# design.net
KiCad netlist of a schematic drawn in Altium Designer
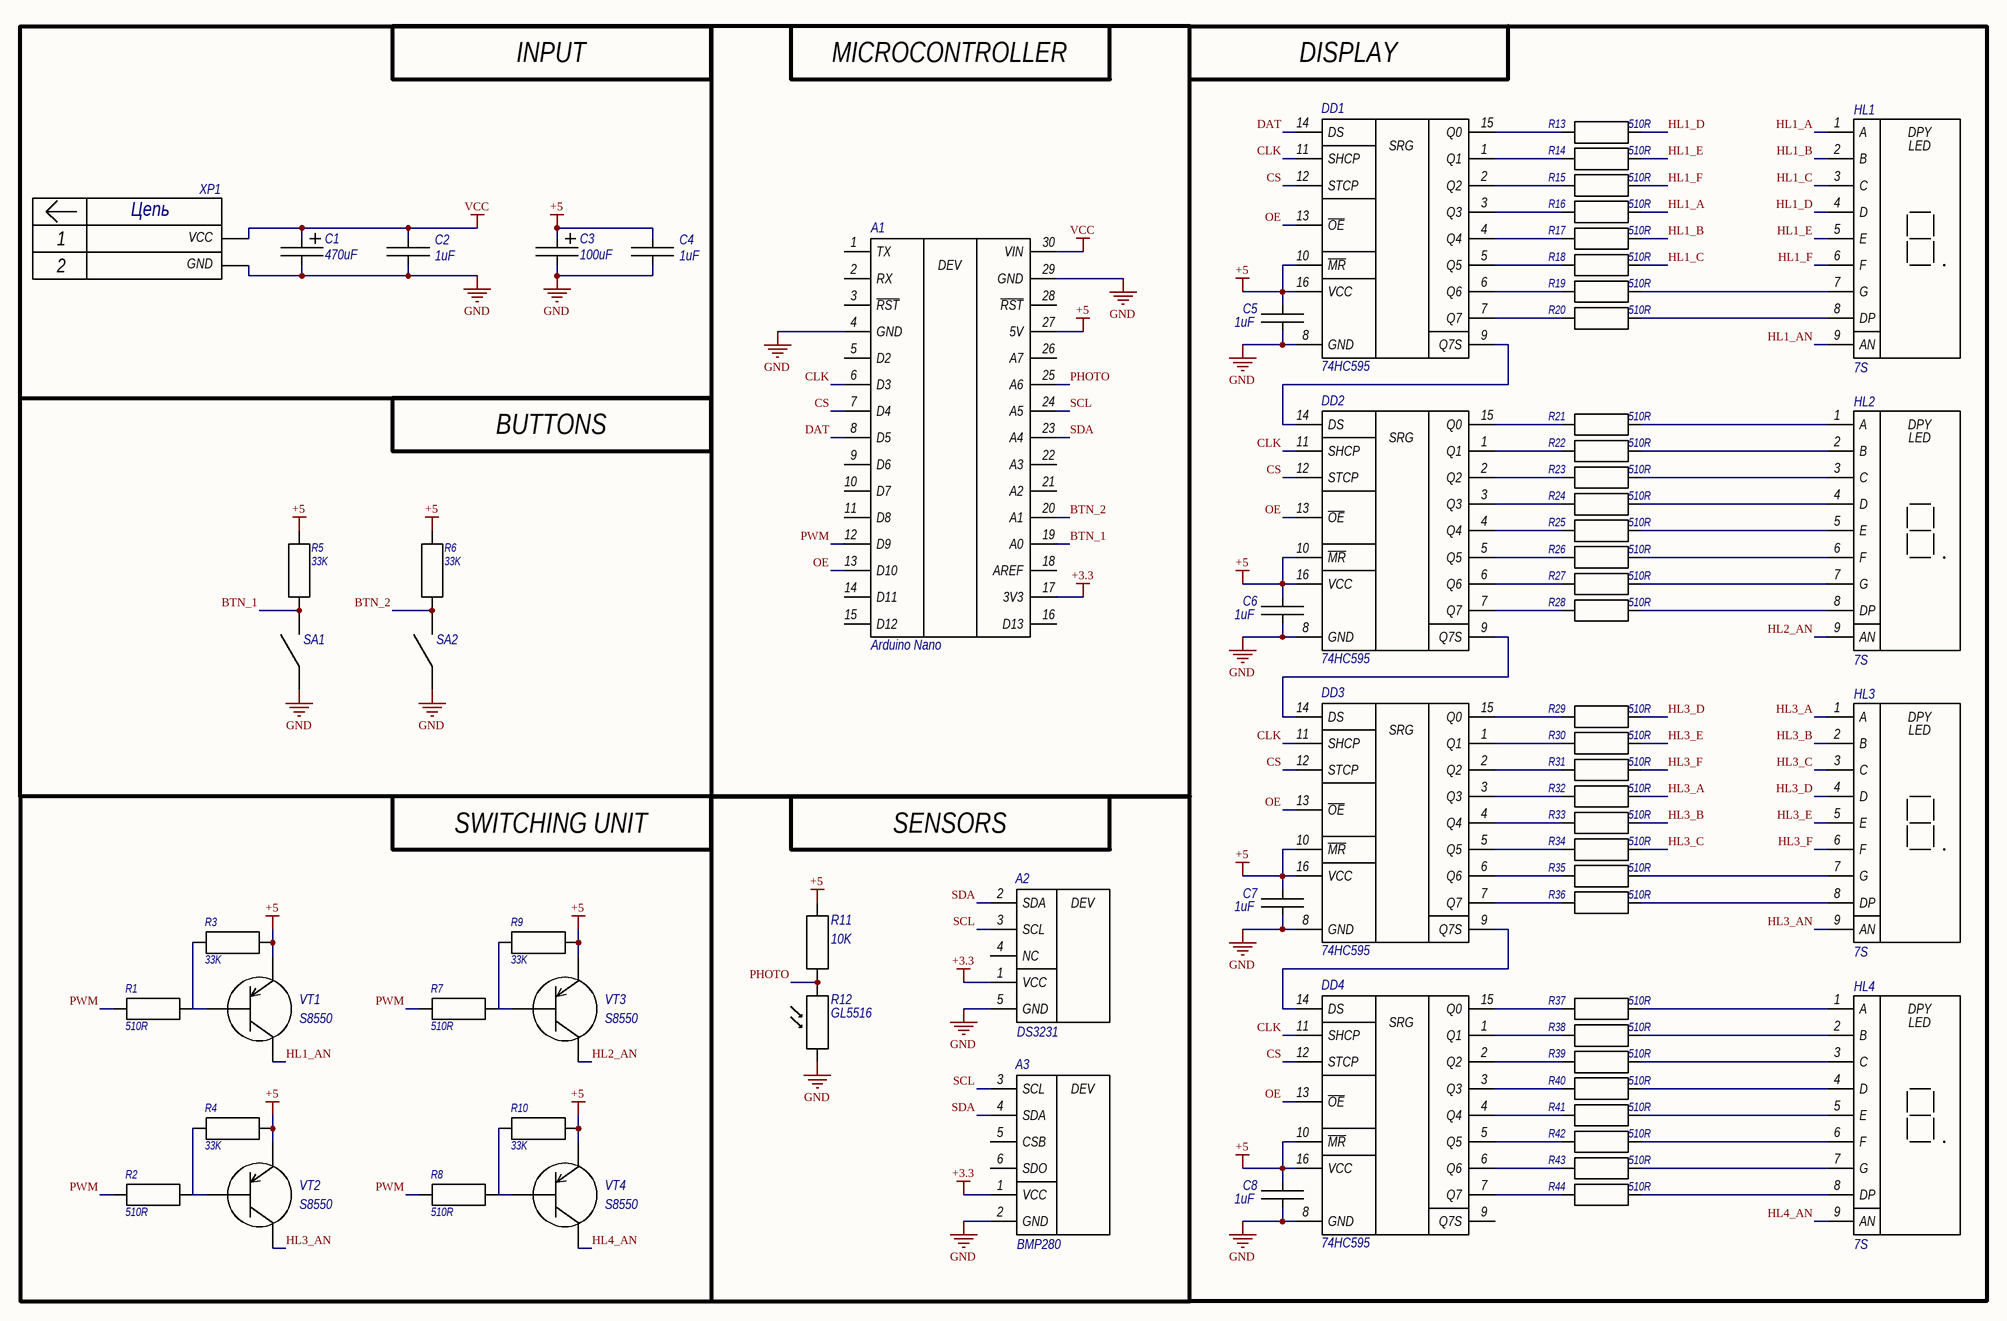
[diagram p0: Схема_часов.SchDoc]

(export (version "E")
  (design (tool "Eeschema 10.0.6"))
  (components
    (comp (ref "A1")
      (value "Arduino Nano")
      (footprint "ArduinoNano")
      (libsource (lib "Schlib1") (part "ArduinoNano"))
    )
    (comp (ref "A2")
      (value "DS3231")
      (footprint "DS3231micro")
      (libsource (lib "Schlib1") (part "DS3231micro"))
    )
    (comp (ref "A3")
      (value "BMP280")
      (footprint "BMP280_Module")
      (libsource (lib "Schlib1") (part "BMP280_Module"))
    )
    (comp (ref "C1")
      (value "470uF")
      (footprint "CAPAER_D0650_L1150_P0250_W50X300")
      (libsource (lib "Schlib1") (part "CPol"))
    )
    (comp (ref "C2")
      (value "1uF")
      (footprint "C0603")
      (description "Ceramic SMT, L*W 1.6x0.8mm, H=(0.8, 0.6)mm")
      (libsource (lib "Schlib1") (part "C0603"))
    )
    (comp (ref "C3")
      (value "100uF")
      (footprint "CAPAE_R0500_X0540(Nich_Case-C5)")
      (libsource (lib "Schlib1") (part "CPol"))
    )
    (comp (ref "C4")
      (value "1uF")
      (footprint "C0603")
      (description "Ceramic SMT, L*W 1.6x0.8mm, H=(0.8, 0.6)mm")
      (libsource (lib "Schlib1") (part "C0603"))
    )
    (comp (ref "C5")
      (value "1uF")
      (footprint "C0603")
      (description "Ceramic SMT, L*W 1.6x0.8mm, H=(0.8, 0.6)mm")
      (libsource (lib "Schlib1") (part "C0603"))
    )
    (comp (ref "C6")
      (value "1uF")
      (footprint "C0603")
      (description "Ceramic SMT, L*W 1.6x0.8mm, H=(0.8, 0.6)mm")
      (libsource (lib "Schlib1") (part "C0603"))
    )
    (comp (ref "C7")
      (value "1uF")
      (footprint "C0603")
      (description "Ceramic SMT, L*W 1.6x0.8mm, H=(0.8, 0.6)mm")
      (libsource (lib "Schlib1") (part "C0603"))
    )
    (comp (ref "C8")
      (value "1uF")
      (footprint "C0603")
      (description "Ceramic SMT, L*W 1.6x0.8mm, H=(0.8, 0.6)mm")
      (libsource (lib "Schlib1") (part "C0603"))
    )
    (comp (ref "DD1") (value "74HC595") (footprint "SO-16") (libsource (lib "Schlib1") (part "74HC595")))
    (comp (ref "DD2") (value "74HC595") (footprint "SO-16") (libsource (lib "Schlib1") (part "74HC595")))
    (comp (ref "DD3") (value "74HC595") (footprint "SO-16") (libsource (lib "Schlib1") (part "74HC595")))
    (comp (ref "DD4") (value "74HC595") (footprint "SO-16") (libsource (lib "Schlib1") (part "74HC595")))
    (comp (ref "HL1") (value "7S") (footprint "7SEG_SA10_21") (libsource (lib "Schlib1") (part "7SEG_AN")))
    (comp (ref "HL2") (value "7S") (footprint "7SEG_SA10_21") (libsource (lib "Schlib1") (part "7SEG_AN")))
    (comp (ref "HL3") (value "7S") (footprint "7SEG_SA10_21") (libsource (lib "Schlib1") (part "7SEG_AN")))
    (comp (ref "HL4") (value "7S") (footprint "7SEG_SA10_21") (libsource (lib "Schlib1") (part "7SEG_AN")))
    (comp (ref "R1")
      (value "510R")
      (footprint "R0805")
      (description "SMT, L*W 2.0x1.25mm, H=0.5mm")
      (libsource (lib "Schlib1") (part "R0805"))
    )
    (comp (ref "R2")
      (value "510R")
      (footprint "R0805")
      (description "SMT, L*W 2.0x1.25mm, H=0.5mm")
      (libsource (lib "Schlib1") (part "R0805"))
    )
    (comp (ref "R3")
      (value "33K")
      (footprint "R0805")
      (description "SMT, L*W 2.0x1.25mm, H=0.5mm")
      (libsource (lib "Schlib1") (part "R0805"))
    )
    (comp (ref "R4")
      (value "33K")
      (footprint "R0805")
      (description "SMT, L*W 2.0x1.25mm, H=0.5mm")
      (libsource (lib "Schlib1") (part "R0805"))
    )
    (comp (ref "R5")
      (value "33K")
      (footprint "R0805")
      (description "SMT, L*W 2.0x1.25mm, H=0.5mm")
      (libsource (lib "Schlib1") (part "R0805"))
    )
    (comp (ref "R6")
      (value "33K")
      (footprint "R0805")
      (description "SMT, L*W 2.0x1.25mm, H=0.5mm")
      (libsource (lib "Schlib1") (part "R0805"))
    )
    (comp (ref "R7")
      (value "510R")
      (footprint "R0805")
      (description "SMT, L*W 2.0x1.25mm, H=0.5mm")
      (libsource (lib "Schlib1") (part "R0805"))
    )
    (comp (ref "R8")
      (value "510R")
      (footprint "R0805")
      (description "SMT, L*W 2.0x1.25mm, H=0.5mm")
      (libsource (lib "Schlib1") (part "R0805"))
    )
    (comp (ref "R9")
      (value "33K")
      (footprint "R0805")
      (description "SMT, L*W 2.0x1.25mm, H=0.5mm")
      (libsource (lib "Schlib1") (part "R0805"))
    )
    (comp (ref "R10")
      (value "33K")
      (footprint "R0805")
      (description "SMT, L*W 2.0x1.25mm, H=0.5mm")
      (libsource (lib "Schlib1") (part "R0805"))
    )
    (comp (ref "R11")
      (value "10K")
      (footprint "R0805")
      (description "SMT, L*W 2.0x1.25mm, H=0.5mm")
      (libsource (lib "Schlib1") (part "R0805"))
    )
    (comp (ref "R12") (value "GL5516") (footprint "GL55") (libsource (lib "Schlib1") (part "Photores")))
    (comp (ref "R13")
      (value "510R")
      (footprint "R0805")
      (description "SMT, L*W 2.0x1.25mm, H=0.5mm")
      (libsource (lib "Schlib1") (part "R0805"))
    )
    (comp (ref "R14")
      (value "510R")
      (footprint "R0805")
      (description "SMT, L*W 2.0x1.25mm, H=0.5mm")
      (libsource (lib "Schlib1") (part "R0805"))
    )
    (comp (ref "R15")
      (value "510R")
      (footprint "R0805")
      (description "SMT, L*W 2.0x1.25mm, H=0.5mm")
      (libsource (lib "Schlib1") (part "R0805"))
    )
    (comp (ref "R16")
      (value "510R")
      (footprint "R0805")
      (description "SMT, L*W 2.0x1.25mm, H=0.5mm")
      (libsource (lib "Schlib1") (part "R0805"))
    )
    (comp (ref "R17")
      (value "510R")
      (footprint "R0805")
      (description "SMT, L*W 2.0x1.25mm, H=0.5mm")
      (libsource (lib "Schlib1") (part "R0805"))
    )
    (comp (ref "R18")
      (value "510R")
      (footprint "R0805")
      (description "SMT, L*W 2.0x1.25mm, H=0.5mm")
      (libsource (lib "Schlib1") (part "R0805"))
    )
    (comp (ref "R19")
      (value "510R")
      (footprint "R0805")
      (description "SMT, L*W 2.0x1.25mm, H=0.5mm")
      (libsource (lib "Schlib1") (part "R0805"))
    )
    (comp (ref "R20")
      (value "510R")
      (footprint "R0805")
      (description "SMT, L*W 2.0x1.25mm, H=0.5mm")
      (libsource (lib "Schlib1") (part "R0805"))
    )
    (comp (ref "R21")
      (value "510R")
      (footprint "R0805")
      (description "SMT, L*W 2.0x1.25mm, H=0.5mm")
      (libsource (lib "Schlib1") (part "R0805"))
    )
    (comp (ref "R22")
      (value "510R")
      (footprint "R0805")
      (description "SMT, L*W 2.0x1.25mm, H=0.5mm")
      (libsource (lib "Schlib1") (part "R0805"))
    )
    (comp (ref "R23")
      (value "510R")
      (footprint "R0805")
      (description "SMT, L*W 2.0x1.25mm, H=0.5mm")
      (libsource (lib "Schlib1") (part "R0805"))
    )
    (comp (ref "R24")
      (value "510R")
      (footprint "R0805")
      (description "SMT, L*W 2.0x1.25mm, H=0.5mm")
      (libsource (lib "Schlib1") (part "R0805"))
    )
    (comp (ref "R25")
      (value "510R")
      (footprint "R0805")
      (description "SMT, L*W 2.0x1.25mm, H=0.5mm")
      (libsource (lib "Schlib1") (part "R0805"))
    )
    (comp (ref "R26")
      (value "510R")
      (footprint "R0805")
      (description "SMT, L*W 2.0x1.25mm, H=0.5mm")
      (libsource (lib "Schlib1") (part "R0805"))
    )
    (comp (ref "R27")
      (value "510R")
      (footprint "R0805")
      (description "SMT, L*W 2.0x1.25mm, H=0.5mm")
      (libsource (lib "Schlib1") (part "R0805"))
    )
    (comp (ref "R28")
      (value "510R")
      (footprint "R0805")
      (description "SMT, L*W 2.0x1.25mm, H=0.5mm")
      (libsource (lib "Schlib1") (part "R0805"))
    )
    (comp (ref "R29")
      (value "510R")
      (footprint "R0805")
      (description "SMT, L*W 2.0x1.25mm, H=0.5mm")
      (libsource (lib "Schlib1") (part "R0805"))
    )
    (comp (ref "R30")
      (value "510R")
      (footprint "R0805")
      (description "SMT, L*W 2.0x1.25mm, H=0.5mm")
      (libsource (lib "Schlib1") (part "R0805"))
    )
    (comp (ref "R31")
      (value "510R")
      (footprint "R0805")
      (description "SMT, L*W 2.0x1.25mm, H=0.5mm")
      (libsource (lib "Schlib1") (part "R0805"))
    )
    (comp (ref "R32")
      (value "510R")
      (footprint "R0805")
      (description "SMT, L*W 2.0x1.25mm, H=0.5mm")
      (libsource (lib "Schlib1") (part "R0805"))
    )
    (comp (ref "R33")
      (value "510R")
      (footprint "R0805")
      (description "SMT, L*W 2.0x1.25mm, H=0.5mm")
      (libsource (lib "Schlib1") (part "R0805"))
    )
    (comp (ref "R34")
      (value "510R")
      (footprint "R0805")
      (description "SMT, L*W 2.0x1.25mm, H=0.5mm")
      (libsource (lib "Schlib1") (part "R0805"))
    )
    (comp (ref "R35")
      (value "510R")
      (footprint "R0805")
      (description "SMT, L*W 2.0x1.25mm, H=0.5mm")
      (libsource (lib "Schlib1") (part "R0805"))
    )
    (comp (ref "R36")
      (value "510R")
      (footprint "R0805")
      (description "SMT, L*W 2.0x1.25mm, H=0.5mm")
      (libsource (lib "Schlib1") (part "R0805"))
    )
    (comp (ref "R37")
      (value "510R")
      (footprint "R0805")
      (description "SMT, L*W 2.0x1.25mm, H=0.5mm")
      (libsource (lib "Schlib1") (part "R0805"))
    )
    (comp (ref "R38")
      (value "510R")
      (footprint "R0805")
      (description "SMT, L*W 2.0x1.25mm, H=0.5mm")
      (libsource (lib "Schlib1") (part "R0805"))
    )
    (comp (ref "R39")
      (value "510R")
      (footprint "R0805")
      (description "SMT, L*W 2.0x1.25mm, H=0.5mm")
      (libsource (lib "Schlib1") (part "R0805"))
    )
    (comp (ref "R40")
      (value "510R")
      (footprint "R0805")
      (description "SMT, L*W 2.0x1.25mm, H=0.5mm")
      (libsource (lib "Schlib1") (part "R0805"))
    )
    (comp (ref "R41")
      (value "510R")
      (footprint "R0805")
      (description "SMT, L*W 2.0x1.25mm, H=0.5mm")
      (libsource (lib "Schlib1") (part "R0805"))
    )
    (comp (ref "R42")
      (value "510R")
      (footprint "R0805")
      (description "SMT, L*W 2.0x1.25mm, H=0.5mm")
      (libsource (lib "Schlib1") (part "R0805"))
    )
    (comp (ref "R43")
      (value "510R")
      (footprint "R0805")
      (description "SMT, L*W 2.0x1.25mm, H=0.5mm")
      (libsource (lib "Schlib1") (part "R0805"))
    )
    (comp (ref "R44")
      (value "510R")
      (footprint "R0805")
      (description "SMT, L*W 2.0x1.25mm, H=0.5mm")
      (libsource (lib "Schlib1") (part "R0805"))
    )
    (comp (ref "SA1") (value "~") (footprint "TS6606-9.0") (libsource (lib "Schlib1") (part "SW")))
    (comp (ref "SA2") (value "~") (footprint "TS6606-9.0") (libsource (lib "Schlib1") (part "SW")))
    (comp (ref "VT1")
      (value "~")
      (footprint "S8550")
      (fields (field (name "MODEL") "S8550"))
      (libsource (lib "Schlib1") (part "TRANS-PNP"))
    )
    (comp (ref "VT2")
      (value "~")
      (footprint "S8550")
      (fields (field (name "MODEL") "S8550"))
      (libsource (lib "Schlib1") (part "TRANS-PNP"))
    )
    (comp (ref "VT3")
      (value "~")
      (footprint "S8550")
      (fields (field (name "MODEL") "S8550"))
      (libsource (lib "Schlib1") (part "TRANS-PNP"))
    )
    (comp (ref "VT4")
      (value "~")
      (footprint "S8550")
      (fields (field (name "MODEL") "S8550"))
      (libsource (lib "Schlib1") (part "TRANS-PNP"))
    )
    (comp (ref "XP1")
      (value "DS1072-2MVT6")
      (footprint "PLS2-2")
      (description "2-pin Straight connector PWL-2")
      (fields
        (field (name "MANUFACTURER") "Connfly")
        (field (name "VOLTAGE") "250Vac")
        (field (name "NET 2") "GND")
        (field (name "NET 1") "VCC")
      )
      (libsource (lib "Schlib1") (part "DS1072-2MVT6"))
    )
  )
  (nets
    (net (code "1") (name "+3.3") (class "Default")
      (node (ref "A1") (pin "17") (pinfunction "3V3_17") (pintype "passive"))
      (node (ref "A2") (pin "1") (pinfunction "VCC_1") (pintype "passive"))
      (node (ref "A3") (pin "1") (pinfunction "VCC_1") (pintype "passive"))
    )
    (net (code "2") (name "+5") (class "Default")
      (node (ref "A1") (pin "27") (pinfunction "5V_27") (pintype "passive"))
      (node (ref "C3") (pin "1") (pinfunction "1_1") (pintype "passive"))
      (node (ref "C4") (pin "2") (pinfunction "2_2") (pintype "passive"))
      (node (ref "C5") (pin "1") (pinfunction "1_1") (pintype "passive"))
      (node (ref "C6") (pin "1") (pinfunction "1_1") (pintype "passive"))
      (node (ref "C7") (pin "1") (pinfunction "1_1") (pintype "passive"))
      (node (ref "C8") (pin "1") (pinfunction "1_1") (pintype "passive"))
      (node (ref "DD1") (pin "10") (pinfunction "~{MR}_10") (pintype "passive"))
      (node (ref "DD1") (pin "16") (pinfunction "VCC_16") (pintype "passive"))
      (node (ref "DD2") (pin "10") (pinfunction "~{MR}_10") (pintype "passive"))
      (node (ref "DD2") (pin "16") (pinfunction "VCC_16") (pintype "passive"))
      (node (ref "DD3") (pin "10") (pinfunction "~{MR}_10") (pintype "passive"))
      (node (ref "DD3") (pin "16") (pinfunction "VCC_16") (pintype "passive"))
      (node (ref "DD4") (pin "10") (pinfunction "~{MR}_10") (pintype "passive"))
      (node (ref "DD4") (pin "16") (pinfunction "VCC_16") (pintype "passive"))
      (node (ref "R10") (pin "1") (pinfunction "1_1") (pintype "passive"))
      (node (ref "R11") (pin "1") (pinfunction "1_1") (pintype "passive"))
      (node (ref "R3") (pin "1") (pinfunction "1_1") (pintype "passive"))
      (node (ref "R4") (pin "1") (pinfunction "1_1") (pintype "passive"))
      (node (ref "R5") (pin "1") (pinfunction "1_1") (pintype "passive"))
      (node (ref "R6") (pin "1") (pinfunction "1_1") (pintype "passive"))
      (node (ref "R9") (pin "1") (pinfunction "1_1") (pintype "passive"))
      (node (ref "VT1") (pin "E") (pinfunction "E_E") (pintype "passive"))
      (node (ref "VT2") (pin "E") (pinfunction "E_E") (pintype "passive"))
      (node (ref "VT3") (pin "E") (pinfunction "E_E") (pintype "passive"))
      (node (ref "VT4") (pin "E") (pinfunction "E_E") (pintype "passive"))
    )
    (net (code "3") (name "/BTN_1") (class "Default")
      (node (ref "A1") (pin "19") (pinfunction "A0_19") (pintype "passive"))
      (node (ref "R5") (pin "2") (pinfunction "2_2") (pintype "passive"))
      (node (ref "SA1") (pin "1") (pinfunction "1_1") (pintype "passive"))
    )
    (net (code "4") (name "/BTN_2") (class "Default")
      (node (ref "A1") (pin "20") (pinfunction "A1_20") (pintype "passive"))
      (node (ref "R6") (pin "2") (pinfunction "2_2") (pintype "passive"))
      (node (ref "SA2") (pin "1") (pinfunction "1_1") (pintype "passive"))
    )
    (net (code "5") (name "/CLK") (class "Default")
      (node (ref "A1") (pin "6") (pinfunction "D3_6") (pintype "passive"))
      (node (ref "DD1") (pin "11") (pinfunction "SHCP_11") (pintype "passive"))
      (node (ref "DD2") (pin "11") (pinfunction "SHCP_11") (pintype "passive"))
      (node (ref "DD3") (pin "11") (pinfunction "SHCP_11") (pintype "passive"))
      (node (ref "DD4") (pin "11") (pinfunction "SHCP_11") (pintype "passive"))
    )
    (net (code "6") (name "/CS") (class "Default")
      (node (ref "A1") (pin "7") (pinfunction "D4_7") (pintype "passive"))
      (node (ref "DD1") (pin "12") (pinfunction "STCP_12") (pintype "passive"))
      (node (ref "DD2") (pin "12") (pinfunction "STCP_12") (pintype "passive"))
      (node (ref "DD3") (pin "12") (pinfunction "STCP_12") (pintype "passive"))
      (node (ref "DD4") (pin "12") (pinfunction "STCP_12") (pintype "passive"))
    )
    (net (code "7") (name "/DAT") (class "Default")
      (node (ref "A1") (pin "8") (pinfunction "D5_8") (pintype "passive"))
      (node (ref "DD1") (pin "14") (pinfunction "DS_14") (pintype "passive"))
    )
    (net (code "8") (name "/HL1_A") (class "Default")
      (node (ref "HL1") (pin "1") (pinfunction "A_1") (pintype "passive"))
      (node (ref "R16") (pin "1") (pinfunction "1_1") (pintype "passive"))
    )
    (net (code "9") (name "/HL1_AN") (class "Default")
      (node (ref "HL1") (pin "9") (pinfunction "AN_9") (pintype "passive"))
      (node (ref "VT1") (pin "C") (pinfunction "C_C") (pintype "passive"))
    )
    (net (code "10") (name "/HL1_B") (class "Default")
      (node (ref "HL1") (pin "2") (pinfunction "B_2") (pintype "passive"))
      (node (ref "R17") (pin "1") (pinfunction "1_1") (pintype "passive"))
    )
    (net (code "11") (name "/HL1_C") (class "Default")
      (node (ref "HL1") (pin "3") (pinfunction "C_3") (pintype "passive"))
      (node (ref "R18") (pin "1") (pinfunction "1_1") (pintype "passive"))
    )
    (net (code "12") (name "/HL1_D") (class "Default")
      (node (ref "HL1") (pin "4") (pinfunction "D_4") (pintype "passive"))
      (node (ref "R13") (pin "1") (pinfunction "1_1") (pintype "passive"))
    )
    (net (code "13") (name "/HL1_E") (class "Default")
      (node (ref "HL1") (pin "5") (pinfunction "E_5") (pintype "passive"))
      (node (ref "R14") (pin "1") (pinfunction "1_1") (pintype "passive"))
    )
    (net (code "14") (name "/HL1_F") (class "Default")
      (node (ref "HL1") (pin "6") (pinfunction "F_6") (pintype "passive"))
      (node (ref "R15") (pin "1") (pinfunction "1_1") (pintype "passive"))
    )
    (net (code "15") (name "/HL2_AN") (class "Default")
      (node (ref "HL2") (pin "9") (pinfunction "AN_9") (pintype "passive"))
      (node (ref "VT3") (pin "C") (pinfunction "C_C") (pintype "passive"))
    )
    (net (code "16") (name "/HL3_A") (class "Default")
      (node (ref "HL3") (pin "1") (pinfunction "A_1") (pintype "passive"))
      (node (ref "R32") (pin "1") (pinfunction "1_1") (pintype "passive"))
    )
    (net (code "17") (name "/HL3_AN") (class "Default")
      (node (ref "HL3") (pin "9") (pinfunction "AN_9") (pintype "passive"))
      (node (ref "VT2") (pin "C") (pinfunction "C_C") (pintype "passive"))
    )
    (net (code "18") (name "/HL3_B") (class "Default")
      (node (ref "HL3") (pin "2") (pinfunction "B_2") (pintype "passive"))
      (node (ref "R33") (pin "1") (pinfunction "1_1") (pintype "passive"))
    )
    (net (code "19") (name "/HL3_C") (class "Default")
      (node (ref "HL3") (pin "3") (pinfunction "C_3") (pintype "passive"))
      (node (ref "R34") (pin "1") (pinfunction "1_1") (pintype "passive"))
    )
    (net (code "20") (name "/HL3_D") (class "Default")
      (node (ref "HL3") (pin "4") (pinfunction "D_4") (pintype "passive"))
      (node (ref "R29") (pin "1") (pinfunction "1_1") (pintype "passive"))
    )
    (net (code "21") (name "/HL3_E") (class "Default")
      (node (ref "HL3") (pin "5") (pinfunction "E_5") (pintype "passive"))
      (node (ref "R30") (pin "1") (pinfunction "1_1") (pintype "passive"))
    )
    (net (code "22") (name "/HL3_F") (class "Default")
      (node (ref "HL3") (pin "6") (pinfunction "F_6") (pintype "passive"))
      (node (ref "R31") (pin "1") (pinfunction "1_1") (pintype "passive"))
    )
    (net (code "23") (name "/HL4_AN") (class "Default")
      (node (ref "HL4") (pin "9") (pinfunction "AN_9") (pintype "passive"))
      (node (ref "VT4") (pin "C") (pinfunction "C_C") (pintype "passive"))
    )
    (net (code "24") (name "/OE") (class "Default")
      (node (ref "A1") (pin "13") (pinfunction "D10_13") (pintype "passive"))
      (node (ref "DD1") (pin "13") (pinfunction "~{OE}_13") (pintype "passive"))
      (node (ref "DD2") (pin "13") (pinfunction "~{OE}_13") (pintype "passive"))
      (node (ref "DD3") (pin "13") (pinfunction "~{OE}_13") (pintype "passive"))
      (node (ref "DD4") (pin "13") (pinfunction "~{OE}_13") (pintype "passive"))
    )
    (net (code "25") (name "/PHOTO") (class "Default")
      (node (ref "A1") (pin "25") (pinfunction "A6_25") (pintype "passive"))
      (node (ref "R11") (pin "2") (pinfunction "2_2") (pintype "passive"))
      (node (ref "R12") (pin "1") (pinfunction "1_1") (pintype "passive"))
    )
    (net (code "26") (name "/PWM") (class "Default")
      (node (ref "A1") (pin "12") (pinfunction "D9_12") (pintype "passive"))
      (node (ref "R1") (pin "2") (pinfunction "2_2") (pintype "passive"))
      (node (ref "R2") (pin "2") (pinfunction "2_2") (pintype "passive"))
      (node (ref "R7") (pin "2") (pinfunction "2_2") (pintype "passive"))
      (node (ref "R8") (pin "2") (pinfunction "2_2") (pintype "passive"))
    )
    (net (code "27") (name "/SCL") (class "Default")
      (node (ref "A1") (pin "24") (pinfunction "A5_24") (pintype "passive"))
      (node (ref "A2") (pin "3") (pinfunction "SCL_3") (pintype "passive"))
      (node (ref "A3") (pin "3") (pinfunction "SCL_3") (pintype "passive"))
    )
    (net (code "28") (name "/SDA") (class "Default")
      (node (ref "A1") (pin "23") (pinfunction "A4_23") (pintype "passive"))
      (node (ref "A2") (pin "2") (pinfunction "SDA_2") (pintype "passive"))
      (node (ref "A3") (pin "4") (pinfunction "SDA_4") (pintype "passive"))
    )
    (net (code "29") (name "GND") (class "Default")
      (node (ref "A1") (pin "29") (pinfunction "GND_29") (pintype "passive"))
      (node (ref "A1") (pin "4") (pinfunction "GND_4") (pintype "passive"))
      (node (ref "A2") (pin "5") (pinfunction "GND_5") (pintype "passive"))
      (node (ref "A3") (pin "2") (pinfunction "GND_2") (pintype "passive"))
      (node (ref "C1") (pin "2") (pinfunction "2_2") (pintype "passive"))
      (node (ref "C2") (pin "1") (pinfunction "1_1") (pintype "passive"))
      (node (ref "C3") (pin "2") (pinfunction "2_2") (pintype "passive"))
      (node (ref "C4") (pin "1") (pinfunction "1_1") (pintype "passive"))
      (node (ref "C5") (pin "2") (pinfunction "2_2") (pintype "passive"))
      (node (ref "C6") (pin "2") (pinfunction "2_2") (pintype "passive"))
      (node (ref "C7") (pin "2") (pinfunction "2_2") (pintype "passive"))
      (node (ref "C8") (pin "2") (pinfunction "2_2") (pintype "passive"))
      (node (ref "DD1") (pin "8") (pinfunction "GND_8") (pintype "passive"))
      (node (ref "DD2") (pin "8") (pinfunction "GND_8") (pintype "passive"))
      (node (ref "DD3") (pin "8") (pinfunction "GND_8") (pintype "passive"))
      (node (ref "DD4") (pin "8") (pinfunction "GND_8") (pintype "passive"))
      (node (ref "R12") (pin "2") (pinfunction "2_2") (pintype "passive"))
      (node (ref "SA1") (pin "2") (pinfunction "2_2") (pintype "passive"))
      (node (ref "SA2") (pin "2") (pinfunction "2_2") (pintype "passive"))
      (node (ref "XP1") (pin "2") (pinfunction "2_2") (pintype "passive"))
    )
    (net (code "30") (name "Net-(DD1-Q0)") (class "Default")
      (node (ref "DD1") (pin "15") (pinfunction "Q0_15") (pintype "passive"))
      (node (ref "R13") (pin "2") (pinfunction "2_2") (pintype "passive"))
    )
    (net (code "31") (name "Net-(DD1-Q1)") (class "Default")
      (node (ref "DD1") (pin "1") (pinfunction "Q1_1") (pintype "passive"))
      (node (ref "R14") (pin "2") (pinfunction "2_2") (pintype "passive"))
    )
    (net (code "32") (name "Net-(DD1-Q2)") (class "Default")
      (node (ref "DD1") (pin "2") (pinfunction "Q2_2") (pintype "passive"))
      (node (ref "R15") (pin "2") (pinfunction "2_2") (pintype "passive"))
    )
    (net (code "33") (name "Net-(DD1-Q3)") (class "Default")
      (node (ref "DD1") (pin "3") (pinfunction "Q3_3") (pintype "passive"))
      (node (ref "R16") (pin "2") (pinfunction "2_2") (pintype "passive"))
    )
    (net (code "34") (name "Net-(DD1-Q4)") (class "Default")
      (node (ref "DD1") (pin "4") (pinfunction "Q4_4") (pintype "passive"))
      (node (ref "R17") (pin "2") (pinfunction "2_2") (pintype "passive"))
    )
    (net (code "35") (name "Net-(DD1-Q5)") (class "Default")
      (node (ref "DD1") (pin "5") (pinfunction "Q5_5") (pintype "passive"))
      (node (ref "R18") (pin "2") (pinfunction "2_2") (pintype "passive"))
    )
    (net (code "36") (name "Net-(DD1-Q6)") (class "Default")
      (node (ref "DD1") (pin "6") (pinfunction "Q6_6") (pintype "passive"))
      (node (ref "R19") (pin "2") (pinfunction "2_2") (pintype "passive"))
    )
    (net (code "37") (name "Net-(DD1-Q7)") (class "Default")
      (node (ref "DD1") (pin "7") (pinfunction "Q7_7") (pintype "passive"))
      (node (ref "R20") (pin "2") (pinfunction "2_2") (pintype "passive"))
    )
    (net (code "38") (name "Net-(DD1-Q7S)") (class "Default")
      (node (ref "DD1") (pin "9") (pinfunction "Q7S_9") (pintype "passive"))
      (node (ref "DD2") (pin "14") (pinfunction "DS_14") (pintype "passive"))
    )
    (net (code "39") (name "Net-(DD2-Q0)") (class "Default")
      (node (ref "DD2") (pin "15") (pinfunction "Q0_15") (pintype "passive"))
      (node (ref "R21") (pin "2") (pinfunction "2_2") (pintype "passive"))
    )
    (net (code "40") (name "Net-(DD2-Q1)") (class "Default")
      (node (ref "DD2") (pin "1") (pinfunction "Q1_1") (pintype "passive"))
      (node (ref "R22") (pin "2") (pinfunction "2_2") (pintype "passive"))
    )
    (net (code "41") (name "Net-(DD2-Q2)") (class "Default")
      (node (ref "DD2") (pin "2") (pinfunction "Q2_2") (pintype "passive"))
      (node (ref "R23") (pin "2") (pinfunction "2_2") (pintype "passive"))
    )
    (net (code "42") (name "Net-(DD2-Q3)") (class "Default")
      (node (ref "DD2") (pin "3") (pinfunction "Q3_3") (pintype "passive"))
      (node (ref "R24") (pin "2") (pinfunction "2_2") (pintype "passive"))
    )
    (net (code "43") (name "Net-(DD2-Q4)") (class "Default")
      (node (ref "DD2") (pin "4") (pinfunction "Q4_4") (pintype "passive"))
      (node (ref "R25") (pin "2") (pinfunction "2_2") (pintype "passive"))
    )
    (net (code "44") (name "Net-(DD2-Q5)") (class "Default")
      (node (ref "DD2") (pin "5") (pinfunction "Q5_5") (pintype "passive"))
      (node (ref "R26") (pin "2") (pinfunction "2_2") (pintype "passive"))
    )
    (net (code "45") (name "Net-(DD2-Q6)") (class "Default")
      (node (ref "DD2") (pin "6") (pinfunction "Q6_6") (pintype "passive"))
      (node (ref "R27") (pin "2") (pinfunction "2_2") (pintype "passive"))
    )
    (net (code "46") (name "Net-(DD2-Q7)") (class "Default")
      (node (ref "DD2") (pin "7") (pinfunction "Q7_7") (pintype "passive"))
      (node (ref "R28") (pin "2") (pinfunction "2_2") (pintype "passive"))
    )
    (net (code "47") (name "Net-(DD2-Q7S)") (class "Default")
      (node (ref "DD2") (pin "9") (pinfunction "Q7S_9") (pintype "passive"))
      (node (ref "DD3") (pin "14") (pinfunction "DS_14") (pintype "passive"))
    )
    (net (code "48") (name "Net-(DD3-Q0)") (class "Default")
      (node (ref "DD3") (pin "15") (pinfunction "Q0_15") (pintype "passive"))
      (node (ref "R29") (pin "2") (pinfunction "2_2") (pintype "passive"))
    )
    (net (code "49") (name "Net-(DD3-Q1)") (class "Default")
      (node (ref "DD3") (pin "1") (pinfunction "Q1_1") (pintype "passive"))
      (node (ref "R30") (pin "2") (pinfunction "2_2") (pintype "passive"))
    )
    (net (code "50") (name "Net-(DD3-Q2)") (class "Default")
      (node (ref "DD3") (pin "2") (pinfunction "Q2_2") (pintype "passive"))
      (node (ref "R31") (pin "2") (pinfunction "2_2") (pintype "passive"))
    )
    (net (code "51") (name "Net-(DD3-Q3)") (class "Default")
      (node (ref "DD3") (pin "3") (pinfunction "Q3_3") (pintype "passive"))
      (node (ref "R32") (pin "2") (pinfunction "2_2") (pintype "passive"))
    )
    (net (code "52") (name "Net-(DD3-Q4)") (class "Default")
      (node (ref "DD3") (pin "4") (pinfunction "Q4_4") (pintype "passive"))
      (node (ref "R33") (pin "2") (pinfunction "2_2") (pintype "passive"))
    )
    (net (code "53") (name "Net-(DD3-Q5)") (class "Default")
      (node (ref "DD3") (pin "5") (pinfunction "Q5_5") (pintype "passive"))
      (node (ref "R34") (pin "2") (pinfunction "2_2") (pintype "passive"))
    )
    (net (code "54") (name "Net-(DD3-Q6)") (class "Default")
      (node (ref "DD3") (pin "6") (pinfunction "Q6_6") (pintype "passive"))
      (node (ref "R35") (pin "2") (pinfunction "2_2") (pintype "passive"))
    )
    (net (code "55") (name "Net-(DD3-Q7)") (class "Default")
      (node (ref "DD3") (pin "7") (pinfunction "Q7_7") (pintype "passive"))
      (node (ref "R36") (pin "2") (pinfunction "2_2") (pintype "passive"))
    )
    (net (code "56") (name "Net-(DD3-Q7S)") (class "Default")
      (node (ref "DD3") (pin "9") (pinfunction "Q7S_9") (pintype "passive"))
      (node (ref "DD4") (pin "14") (pinfunction "DS_14") (pintype "passive"))
    )
    (net (code "57") (name "Net-(DD4-Q0)") (class "Default")
      (node (ref "DD4") (pin "15") (pinfunction "Q0_15") (pintype "passive"))
      (node (ref "R37") (pin "2") (pinfunction "2_2") (pintype "passive"))
    )
    (net (code "58") (name "Net-(DD4-Q1)") (class "Default")
      (node (ref "DD4") (pin "1") (pinfunction "Q1_1") (pintype "passive"))
      (node (ref "R38") (pin "2") (pinfunction "2_2") (pintype "passive"))
    )
    (net (code "59") (name "Net-(DD4-Q2)") (class "Default")
      (node (ref "DD4") (pin "2") (pinfunction "Q2_2") (pintype "passive"))
      (node (ref "R39") (pin "2") (pinfunction "2_2") (pintype "passive"))
    )
    (net (code "60") (name "Net-(DD4-Q3)") (class "Default")
      (node (ref "DD4") (pin "3") (pinfunction "Q3_3") (pintype "passive"))
      (node (ref "R40") (pin "2") (pinfunction "2_2") (pintype "passive"))
    )
    (net (code "61") (name "Net-(DD4-Q4)") (class "Default")
      (node (ref "DD4") (pin "4") (pinfunction "Q4_4") (pintype "passive"))
      (node (ref "R41") (pin "2") (pinfunction "2_2") (pintype "passive"))
    )
    (net (code "62") (name "Net-(DD4-Q5)") (class "Default")
      (node (ref "DD4") (pin "5") (pinfunction "Q5_5") (pintype "passive"))
      (node (ref "R42") (pin "2") (pinfunction "2_2") (pintype "passive"))
    )
    (net (code "63") (name "Net-(DD4-Q6)") (class "Default")
      (node (ref "DD4") (pin "6") (pinfunction "Q6_6") (pintype "passive"))
      (node (ref "R43") (pin "2") (pinfunction "2_2") (pintype "passive"))
    )
    (net (code "64") (name "Net-(DD4-Q7)") (class "Default")
      (node (ref "DD4") (pin "7") (pinfunction "Q7_7") (pintype "passive"))
      (node (ref "R44") (pin "2") (pinfunction "2_2") (pintype "passive"))
    )
    (net (code "65") (name "Net-(HL1-DP)") (class "Default")
      (node (ref "HL1") (pin "8") (pinfunction "DP_8") (pintype "passive"))
      (node (ref "R20") (pin "1") (pinfunction "1_1") (pintype "passive"))
    )
    (net (code "66") (name "Net-(HL1-G)") (class "Default")
      (node (ref "HL1") (pin "7") (pinfunction "G_7") (pintype "passive"))
      (node (ref "R19") (pin "1") (pinfunction "1_1") (pintype "passive"))
    )
    (net (code "67") (name "Net-(HL2-A)") (class "Default")
      (node (ref "HL2") (pin "1") (pinfunction "A_1") (pintype "passive"))
      (node (ref "R21") (pin "1") (pinfunction "1_1") (pintype "passive"))
    )
    (net (code "68") (name "Net-(HL2-B)") (class "Default")
      (node (ref "HL2") (pin "2") (pinfunction "B_2") (pintype "passive"))
      (node (ref "R22") (pin "1") (pinfunction "1_1") (pintype "passive"))
    )
    (net (code "69") (name "Net-(HL2-C)") (class "Default")
      (node (ref "HL2") (pin "3") (pinfunction "C_3") (pintype "passive"))
      (node (ref "R23") (pin "1") (pinfunction "1_1") (pintype "passive"))
    )
    (net (code "70") (name "Net-(HL2-D)") (class "Default")
      (node (ref "HL2") (pin "4") (pinfunction "D_4") (pintype "passive"))
      (node (ref "R24") (pin "1") (pinfunction "1_1") (pintype "passive"))
    )
    (net (code "71") (name "Net-(HL2-DP)") (class "Default")
      (node (ref "HL2") (pin "8") (pinfunction "DP_8") (pintype "passive"))
      (node (ref "R28") (pin "1") (pinfunction "1_1") (pintype "passive"))
    )
    (net (code "72") (name "Net-(HL2-E)") (class "Default")
      (node (ref "HL2") (pin "5") (pinfunction "E_5") (pintype "passive"))
      (node (ref "R25") (pin "1") (pinfunction "1_1") (pintype "passive"))
    )
    (net (code "73") (name "Net-(HL2-F)") (class "Default")
      (node (ref "HL2") (pin "6") (pinfunction "F_6") (pintype "passive"))
      (node (ref "R26") (pin "1") (pinfunction "1_1") (pintype "passive"))
    )
    (net (code "74") (name "Net-(HL2-G)") (class "Default")
      (node (ref "HL2") (pin "7") (pinfunction "G_7") (pintype "passive"))
      (node (ref "R27") (pin "1") (pinfunction "1_1") (pintype "passive"))
    )
    (net (code "75") (name "Net-(HL3-DP)") (class "Default")
      (node (ref "HL3") (pin "8") (pinfunction "DP_8") (pintype "passive"))
      (node (ref "R36") (pin "1") (pinfunction "1_1") (pintype "passive"))
    )
    (net (code "76") (name "Net-(HL3-G)") (class "Default")
      (node (ref "HL3") (pin "7") (pinfunction "G_7") (pintype "passive"))
      (node (ref "R35") (pin "1") (pinfunction "1_1") (pintype "passive"))
    )
    (net (code "77") (name "Net-(HL4-A)") (class "Default")
      (node (ref "HL4") (pin "1") (pinfunction "A_1") (pintype "passive"))
      (node (ref "R37") (pin "1") (pinfunction "1_1") (pintype "passive"))
    )
    (net (code "78") (name "Net-(HL4-B)") (class "Default")
      (node (ref "HL4") (pin "2") (pinfunction "B_2") (pintype "passive"))
      (node (ref "R38") (pin "1") (pinfunction "1_1") (pintype "passive"))
    )
    (net (code "79") (name "Net-(HL4-C)") (class "Default")
      (node (ref "HL4") (pin "3") (pinfunction "C_3") (pintype "passive"))
      (node (ref "R39") (pin "1") (pinfunction "1_1") (pintype "passive"))
    )
    (net (code "80") (name "Net-(HL4-D)") (class "Default")
      (node (ref "HL4") (pin "4") (pinfunction "D_4") (pintype "passive"))
      (node (ref "R40") (pin "1") (pinfunction "1_1") (pintype "passive"))
    )
    (net (code "81") (name "Net-(HL4-DP)") (class "Default")
      (node (ref "HL4") (pin "8") (pinfunction "DP_8") (pintype "passive"))
      (node (ref "R44") (pin "1") (pinfunction "1_1") (pintype "passive"))
    )
    (net (code "82") (name "Net-(HL4-E)") (class "Default")
      (node (ref "HL4") (pin "5") (pinfunction "E_5") (pintype "passive"))
      (node (ref "R41") (pin "1") (pinfunction "1_1") (pintype "passive"))
    )
    (net (code "83") (name "Net-(HL4-F)") (class "Default")
      (node (ref "HL4") (pin "6") (pinfunction "F_6") (pintype "passive"))
      (node (ref "R42") (pin "1") (pinfunction "1_1") (pintype "passive"))
    )
    (net (code "84") (name "Net-(HL4-G)") (class "Default")
      (node (ref "HL4") (pin "7") (pinfunction "G_7") (pintype "passive"))
      (node (ref "R43") (pin "1") (pinfunction "1_1") (pintype "passive"))
    )
    (net (code "85") (name "Net-(R1-Pad1)") (class "Default")
      (node (ref "R1") (pin "1") (pinfunction "1_1") (pintype "passive"))
      (node (ref "R3") (pin "2") (pinfunction "2_2") (pintype "passive"))
      (node (ref "VT1") (pin "B") (pinfunction "B_B") (pintype "passive"))
    )
    (net (code "86") (name "Net-(R2-Pad1)") (class "Default")
      (node (ref "R2") (pin "1") (pinfunction "1_1") (pintype "passive"))
      (node (ref "R4") (pin "2") (pinfunction "2_2") (pintype "passive"))
      (node (ref "VT2") (pin "B") (pinfunction "B_B") (pintype "passive"))
    )
    (net (code "87") (name "Net-(R7-Pad1)") (class "Default")
      (node (ref "R7") (pin "1") (pinfunction "1_1") (pintype "passive"))
      (node (ref "R9") (pin "2") (pinfunction "2_2") (pintype "passive"))
      (node (ref "VT3") (pin "B") (pinfunction "B_B") (pintype "passive"))
    )
    (net (code "88") (name "Net-(R10-Pad2)") (class "Default")
      (node (ref "R10") (pin "2") (pinfunction "2_2") (pintype "passive"))
      (node (ref "R8") (pin "1") (pinfunction "1_1") (pintype "passive"))
      (node (ref "VT4") (pin "B") (pinfunction "B_B") (pintype "passive"))
    )
    (net (code "89") (name "VCC") (class "Default")
      (node (ref "A1") (pin "30") (pinfunction "VIN_30") (pintype "passive"))
      (node (ref "C1") (pin "1") (pinfunction "1_1") (pintype "passive"))
      (node (ref "C2") (pin "2") (pinfunction "2_2") (pintype "passive"))
      (node (ref "XP1") (pin "1") (pinfunction "1_1") (pintype "passive"))
    )
    (net (code "90") (name "unconnected-(A1-A2-Pad21)") (class "Default")
      (node (ref "A1") (pin "21") (pinfunction "A2_21") (pintype "passive"))
    )
    (net (code "91") (name "unconnected-(A1-A3-Pad22)") (class "Default")
      (node (ref "A1") (pin "22") (pinfunction "A3_22") (pintype "passive"))
    )
    (net (code "92") (name "unconnected-(A1-A7-Pad26)") (class "Default")
      (node (ref "A1") (pin "26") (pinfunction "A7_26") (pintype "passive"))
    )
    (net (code "93") (name "unconnected-(A1-AREF-Pad18)") (class "Default")
      (node (ref "A1") (pin "18") (pinfunction "AREF_18") (pintype "passive"))
    )
    (net (code "94") (name "unconnected-(A1-D2-Pad5)") (class "Default")
      (node (ref "A1") (pin "5") (pinfunction "D2_5") (pintype "passive"))
    )
    (net (code "95") (name "unconnected-(A1-D6-Pad9)") (class "Default")
      (node (ref "A1") (pin "9") (pinfunction "D6_9") (pintype "passive"))
    )
    (net (code "96") (name "unconnected-(A1-D7-Pad10)") (class "Default")
      (node (ref "A1") (pin "10") (pinfunction "D7_10") (pintype "passive"))
    )
    (net (code "97") (name "unconnected-(A1-D8-Pad11)") (class "Default")
      (node (ref "A1") (pin "11") (pinfunction "D8_11") (pintype "passive"))
    )
    (net (code "98") (name "unconnected-(A1-D11-Pad14)") (class "Default")
      (node (ref "A1") (pin "14") (pinfunction "D11_14") (pintype "passive"))
    )
    (net (code "99") (name "unconnected-(A1-D12-Pad15)") (class "Default")
      (node (ref "A1") (pin "15") (pinfunction "D12_15") (pintype "passive"))
    )
    (net (code "100") (name "unconnected-(A1-D13-Pad16)") (class "Default")
      (node (ref "A1") (pin "16") (pinfunction "D13_16") (pintype "passive"))
    )
    (net (code "101") (name "unconnected-(A1-RX-Pad2)") (class "Default")
      (node (ref "A1") (pin "2") (pinfunction "RX_2") (pintype "passive"))
    )
    (net (code "102") (name "unconnected-(A1-TX-Pad1)") (class "Default")
      (node (ref "A1") (pin "1") (pinfunction "TX_1") (pintype "passive"))
    )
    (net (code "103") (name "unconnected-(A1-~{RST}-Pad3)") (class "Default")
      (node (ref "A1") (pin "3") (pinfunction "~{RST}_3") (pintype "passive"))
    )
    (net (code "104") (name "unconnected-(A1-~{RST}-Pad28)") (class "Default")
      (node (ref "A1") (pin "28") (pinfunction "~{RST}_28") (pintype "passive"))
    )
    (net (code "105") (name "unconnected-(A2-NC-Pad4)") (class "Default")
      (node (ref "A2") (pin "4") (pinfunction "NC_4") (pintype "passive"))
    )
    (net (code "106") (name "unconnected-(A3-CSB-Pad5)") (class "Default")
      (node (ref "A3") (pin "5") (pinfunction "CSB_5") (pintype "passive"))
    )
    (net (code "107") (name "unconnected-(A3-SDO-Pad6)") (class "Default")
      (node (ref "A3") (pin "6") (pinfunction "SDO_6") (pintype "passive"))
    )
    (net (code "108") (name "unconnected-(DD4-Q7S-Pad9)") (class "Default")
      (node (ref "DD4") (pin "9") (pinfunction "Q7S_9") (pintype "passive"))
    )
  )
)
